# Motor_Driver.net
KiCad netlist of a schematic drawn in Altium Designer
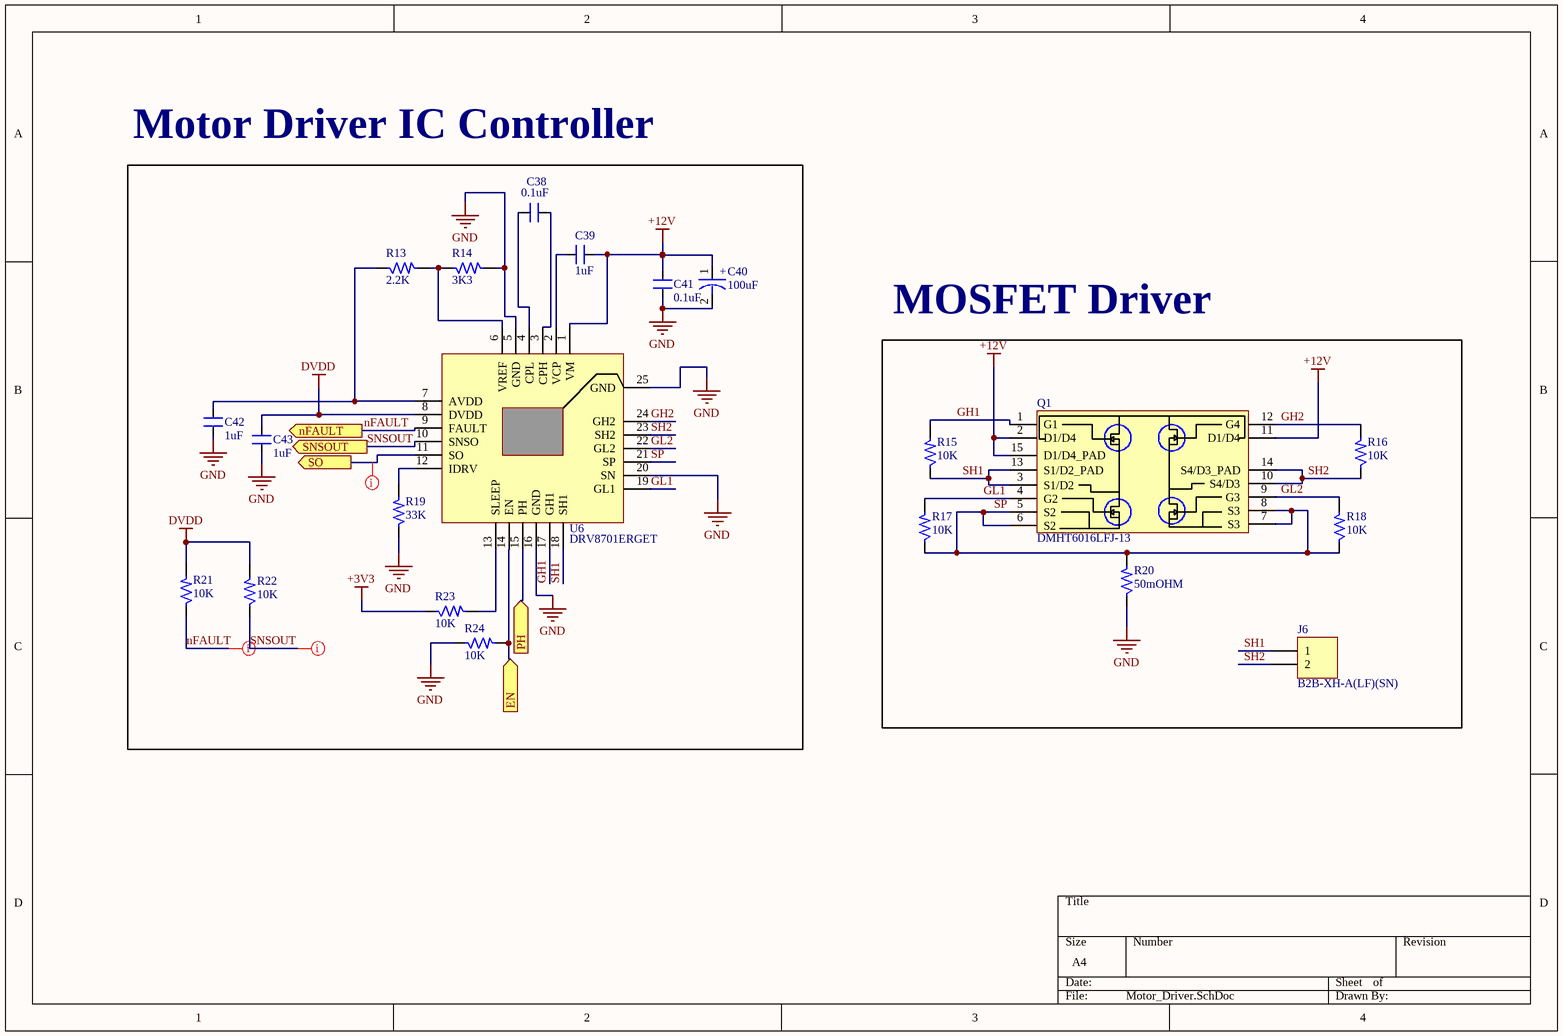
[diagram p0: Motor_Driver.SchDoc]

(export (version "E")
  (design (tool "Eeschema 10.0.6"))
  (components
    (comp (ref "C38")
      (value "0.1uF")
      (footprint "CAP_0805")
      (description "0.1µF ±10% 50V Ceramic Capacitor X7R 0805 (2012 Metric)")
      (fields
        (field (name "MANUFACTURER") "Samsung")
        (field (name "MANUFACTURER PART NUMBER") "CL21B104KBCNNNC")
      )
      (libsource (lib "STM32F407_Board") (part "CAP_0.1uF-50V-10%-0805"))
    )
    (comp (ref "C39")
      (value "1uF")
      (footprint "CAP_0805")
      (description "1µF ±5% 50V Ceramic Capacitor X7R 0805 (2012 Metric)")
      (fields
        (field (name "MANUFACTURER") "Samsung")
        (field (name "MANUFACTURER PART NUMBER") "CC0805JKX7R9BB105")
      )
      (libsource (lib "STM32F407_Board") (part "CAP_1uF-50V-5%-0805"))
    )
    (comp (ref "C40")
      (value "100uF")
      (footprint "ACAP_P305_D393_H393_RAD")
      (description "100µF 50V Aluminum Polymer Capacitor Radial, Can - SMD 28mOhm 4000 Hrs @ 125°C")
      (fields
        (field (name "MANUFACTURER") "Nichicon")
        (field (name "MANUFACTURER PART NUMBER") "GYA1H101MCQ1GS")
      )
      (libsource (lib "STM32F407_Board") (part "CAP-P_100uF-50V-20%-RAD"))
    )
    (comp (ref "C41")
      (value "0.1uF")
      (footprint "CAP_0805")
      (description "0.1µF ±10% 50V Ceramic Capacitor X7R 0805 (2012 Metric)")
      (fields
        (field (name "MANUFACTURER") "Samsung")
        (field (name "MANUFACTURER PART NUMBER") "CL21B104KBCNNNC")
      )
      (libsource (lib "STM32F407_Board") (part "CAP_0.1uF-50V-10%-0805"))
    )
    (comp (ref "C42")
      (value "1uF")
      (footprint "CAP_0805")
      (description "1µF ±5% 50V Ceramic Capacitor X7R 0805 (2012 Metric)")
      (fields
        (field (name "MANUFACTURER") "Samsung")
        (field (name "MANUFACTURER PART NUMBER") "CC0805JKX7R9BB105")
      )
      (libsource (lib "STM32F407_Board") (part "CAP_1uF-50V-5%-0805"))
    )
    (comp (ref "C43")
      (value "1uF")
      (footprint "CAP_0805")
      (description "1µF ±5% 50V Ceramic Capacitor X7R 0805 (2012 Metric)")
      (fields
        (field (name "MANUFACTURER") "Samsung")
        (field (name "MANUFACTURER PART NUMBER") "CC0805JKX7R9BB105")
      )
      (libsource (lib "STM32F407_Board") (part "CAP_1uF-50V-5%-0805"))
    )
    (comp (ref "J6")
      (value "B2B-XH-A(LF)(SN)")
      (footprint "CON2_100_B2B-XH-A_TH_ST")
      (description "2 Pins, 1 Row 2.54mm Pitch, Straight Connector, male")
      (fields (field (name "MANUFACTURER") "JST") (field (name "MATING PART NUMBER") "XHP-2"))
      (libsource (lib "STM32F407_Board") (part "CON-PLG_2X1-100-ST-TH"))
    )
    (comp (ref "Q1")
      (value "DMHT6016LFJ-13")
      (footprint "DFN5045-12_33_212_27X15_SMD_1")
      (description "Mosfet Array 4 N-Channel 14.8A (Ta) Surface Mount V-DFN5045-12")
      (fields (field (name "MANUFACTURER") "ON Semiconductor"))
      (libsource (lib "STM32F407_Board") (part "MOSFET-N_60V-14.8A-V-DFN5045-12"))
    )
    (comp (ref "R13")
      (value "2.2K")
      (footprint "RES_0603")
      (description "2.2 kOhms ±1% 0.1W, 1/10W Chip Resistor 0603 (1608 Metric) Automotive AEC-Q200 Thick Film")
      (fields (field (name "MANUFACTURER") "Walsin") (field (name "MANUFACTURER PART NUMBER") "WR06X2201FTL"))
      (libsource (lib "STM32F407_Board") (part "RES_2.2K-0.1W-1%-0603"))
    )
    (comp (ref "R14")
      (value "3K3")
      (footprint "RES_0603")
      (description "3.3 kOhms ±1% 0.1W, 1/10W Chip Resistor 0603 (1608 Metric) Automotive AEC-Q200 Thick Film")
      (fields (field (name "MANUFACTURER") "Wilson") (field (name "MANUFACTURER PART NUMBER") "WR06X3301FTL"))
      (libsource (lib "STM32F407_Board") (part "RES_3.3K-0.1W-1%-0603"))
    )
    (comp (ref "R15")
      (value "10K")
      (footprint "RES_0603")
      (description "10 kOhms ±1% 0.1W, 1/10W Chip Resistor 0603 (1608 Metric) Automotive AEC-Q200 Thick Film")
      (fields (field (name "MANUFACTURER") "Walsin") (field (name "MANUFACTURER PART NUMBER") "WR06X1002FTL"))
      (libsource (lib "STM32F407_Board") (part "RES_10K-0.1W-1%-0603"))
    )
    (comp (ref "R16")
      (value "10K")
      (footprint "RES_0603")
      (description "10 kOhms ±1% 0.1W, 1/10W Chip Resistor 0603 (1608 Metric) Automotive AEC-Q200 Thick Film")
      (fields (field (name "MANUFACTURER") "Walsin") (field (name "MANUFACTURER PART NUMBER") "WR06X1002FTL"))
      (libsource (lib "STM32F407_Board") (part "RES_10K-0.1W-1%-0603"))
    )
    (comp (ref "R17")
      (value "10K")
      (footprint "RES_0603")
      (description "10 kOhms ±1% 0.1W, 1/10W Chip Resistor 0603 (1608 Metric) Automotive AEC-Q200 Thick Film")
      (fields (field (name "MANUFACTURER") "Walsin") (field (name "MANUFACTURER PART NUMBER") "WR06X1002FTL"))
      (libsource (lib "STM32F407_Board") (part "RES_10K-0.1W-1%-0603"))
    )
    (comp (ref "R18")
      (value "10K")
      (footprint "RES_0603")
      (description "10 kOhms ±1% 0.1W, 1/10W Chip Resistor 0603 (1608 Metric) Automotive AEC-Q200 Thick Film")
      (fields (field (name "MANUFACTURER") "Walsin") (field (name "MANUFACTURER PART NUMBER") "WR06X1002FTL"))
      (libsource (lib "STM32F407_Board") (part "RES_10K-0.1W-1%-0603"))
    )
    (comp (ref "R19")
      (value "33K")
      (footprint "RES_0805")
      (fields
        (field (name "MANUFACTURER") "Vishay BCcomponents")
        (field (name "MANUFACTURER PART NUMBER") "CRG0805F33K")
      )
      (libsource (lib "STM32F407_Board") (part "RES_33K-0.125W-1%-0805"))
    )
    (comp (ref "R20")
      (value "50mOHM")
      (footprint "RES_2512")
      (fields
        (field (name "MANUFACTURER") "Yageo")
        (field (name "MANUFACTURER PART NUMBER") "PA2512FKF7W0R05E")
      )
      (libsource (lib "STM32F407_Board") (part "RES_50mOhm-2W-1%-2512"))
    )
    (comp (ref "R21")
      (value "10K")
      (footprint "RES_0603")
      (description "10 kOhms ±1% 0.1W, 1/10W Chip Resistor 0603 (1608 Metric) Automotive AEC-Q200 Thick Film")
      (fields (field (name "MANUFACTURER") "Walsin") (field (name "MANUFACTURER PART NUMBER") "WR06X1002FTL"))
      (libsource (lib "STM32F407_Board") (part "RES_10K-0.1W-1%-0603"))
    )
    (comp (ref "R22")
      (value "10K")
      (footprint "RES_0603")
      (description "10 kOhms ±1% 0.1W, 1/10W Chip Resistor 0603 (1608 Metric) Automotive AEC-Q200 Thick Film")
      (fields (field (name "MANUFACTURER") "Walsin") (field (name "MANUFACTURER PART NUMBER") "WR06X1002FTL"))
      (libsource (lib "STM32F407_Board") (part "RES_10K-0.1W-1%-0603"))
    )
    (comp (ref "R23")
      (value "10K")
      (footprint "RES_0603")
      (description "10 kOhms ±1% 0.1W, 1/10W Chip Resistor 0603 (1608 Metric) Automotive AEC-Q200 Thick Film")
      (fields (field (name "MANUFACTURER") "Walsin") (field (name "MANUFACTURER PART NUMBER") "WR06X1002FTL"))
      (libsource (lib "STM32F407_Board") (part "RES_10K-0.1W-1%-0603"))
    )
    (comp (ref "R24")
      (value "10K")
      (footprint "RES_0603")
      (description "10 kOhms ±1% 0.1W, 1/10W Chip Resistor 0603 (1608 Metric) Automotive AEC-Q200 Thick Film")
      (fields (field (name "MANUFACTURER") "Walsin") (field (name "MANUFACTURER PART NUMBER") "WR06X1002FTL"))
      (libsource (lib "STM32F407_Board") (part "RES_10K-0.1W-1%-0603"))
    )
    (comp (ref "U6")
      (value "DRV8701ERGET")
      (footprint "VFQFN24_19.6_196_12X32_SMD_1")
      (description "Motor Driver Power MOSFET Parallel 24-VQFN (4x4)")
      (fields (field (name "MANUFACTURER") "Texas Instruments"))
      (libsource (lib "STM32F407_Board") (part "IC_DRV8701ERGET"))
    )
  )
  (nets
    (net (code "1") (name "+3V3") (class "Default")
      (node (ref "R23") (pin "1") (pinfunction "1_1") (pintype "passive"))
    )
    (net (code "2") (name "+12V") (class "Default")
      (node (ref "C39") (pin "1") (pinfunction "1_1") (pintype "passive"))
      (node (ref "C40") (pin "1") (pinfunction "1_1") (pintype "passive"))
      (node (ref "C41") (pin "2") (pinfunction "2_2") (pintype "passive"))
      (node (ref "Q1") (pin "11") (pinfunction "D1/D4_11") (pintype "passive"))
      (node (ref "Q1") (pin "15") (pinfunction "D1/D4_PAD_15") (pintype "passive"))
      (node (ref "Q1") (pin "2") (pinfunction "D1/D4_2") (pintype "passive"))
      (node (ref "U6") (pin "1") (pinfunction "VM_1") (pintype "passive"))
    )
    (net (code "3") (name "/EN") (class "Default")
      (node (ref "R24") (pin "2") (pinfunction "2_2") (pintype "passive"))
      (node (ref "U6") (pin "14") (pinfunction "EN_14") (pintype "passive"))
    )
    (net (code "4") (name "/GH1") (class "Default")
      (node (ref "Q1") (pin "1") (pinfunction "G1_1") (pintype "passive"))
      (node (ref "R15") (pin "2") (pinfunction "2_2") (pintype "passive"))
      (node (ref "U6") (pin "17") (pinfunction "GH1_17") (pintype "passive"))
    )
    (net (code "5") (name "/GH2") (class "Default")
      (node (ref "Q1") (pin "12") (pinfunction "G4_12") (pintype "passive"))
      (node (ref "R16") (pin "2") (pinfunction "2_2") (pintype "passive"))
      (node (ref "U6") (pin "24") (pinfunction "GH2_24") (pintype "passive"))
    )
    (net (code "6") (name "/GL1") (class "Default")
      (node (ref "Q1") (pin "4") (pinfunction "G2_4") (pintype "passive"))
      (node (ref "R17") (pin "2") (pinfunction "2_2") (pintype "passive"))
      (node (ref "U6") (pin "19") (pinfunction "GL1_19") (pintype "passive"))
    )
    (net (code "7") (name "/GL2") (class "Default")
      (node (ref "Q1") (pin "9") (pinfunction "G3_9") (pintype "passive"))
      (node (ref "R18") (pin "2") (pinfunction "2_2") (pintype "passive"))
      (node (ref "U6") (pin "22") (pinfunction "GL2_22") (pintype "passive"))
    )
    (net (code "8") (name "/PH") (class "Default")
      (node (ref "U6") (pin "15") (pinfunction "PH_15") (pintype "passive"))
    )
    (net (code "9") (name "/SH1") (class "Default")
      (node (ref "J6") (pin "1") (pinfunction "1_1") (pintype "passive"))
      (node (ref "Q1") (pin "13") (pinfunction "S1/D2_PAD_13") (pintype "passive"))
      (node (ref "Q1") (pin "3") (pinfunction "S1/D2_3") (pintype "passive"))
      (node (ref "R15") (pin "1") (pinfunction "1_1") (pintype "passive"))
      (node (ref "U6") (pin "18") (pinfunction "SH1_18") (pintype "passive"))
    )
    (net (code "10") (name "/SH2") (class "Default")
      (node (ref "J6") (pin "2") (pinfunction "2_2") (pintype "passive"))
      (node (ref "Q1") (pin "10") (pinfunction "S4/D3_10") (pintype "passive"))
      (node (ref "Q1") (pin "14") (pinfunction "S4/D3_PAD_14") (pintype "passive"))
      (node (ref "R16") (pin "1") (pinfunction "1_1") (pintype "passive"))
      (node (ref "U6") (pin "23") (pinfunction "SH2_23") (pintype "passive"))
    )
    (net (code "11") (name "/SNSOUT") (class "Default")
      (node (ref "R22") (pin "1") (pinfunction "1_1") (pintype "passive"))
      (node (ref "U6") (pin "10") (pinfunction "SNSO_10") (pintype "passive"))
    )
    (net (code "12") (name "/SO") (class "Default")
      (node (ref "U6") (pin "11") (pinfunction "SO_11") (pintype "passive"))
    )
    (net (code "13") (name "/SP") (class "Default")
      (node (ref "Q1") (pin "5") (pinfunction "S2_5") (pintype "passive"))
      (node (ref "Q1") (pin "6") (pinfunction "S2_6") (pintype "passive"))
      (node (ref "Q1") (pin "7") (pinfunction "S3_7") (pintype "passive"))
      (node (ref "Q1") (pin "8") (pinfunction "S3_8") (pintype "passive"))
      (node (ref "R17") (pin "1") (pinfunction "1_1") (pintype "passive"))
      (node (ref "R18") (pin "1") (pinfunction "1_1") (pintype "passive"))
      (node (ref "R20") (pin "2") (pinfunction "2_2") (pintype "passive"))
      (node (ref "U6") (pin "21") (pinfunction "SP_21") (pintype "passive"))
    )
    (net (code "14") (name "/nFAULT") (class "Default")
      (node (ref "R21") (pin "1") (pinfunction "1_1") (pintype "passive"))
      (node (ref "U6") (pin "9") (pinfunction "FAULT_9") (pintype "passive"))
    )
    (net (code "15") (name "DVDD") (class "Default")
      (node (ref "C43") (pin "2") (pinfunction "2_2") (pintype "passive"))
      (node (ref "R21") (pin "2") (pinfunction "2_2") (pintype "passive"))
      (node (ref "R22") (pin "2") (pinfunction "2_2") (pintype "passive"))
      (node (ref "U6") (pin "8") (pinfunction "DVDD_8") (pintype "passive"))
    )
    (net (code "16") (name "GND") (class "Default")
      (node (ref "C40") (pin "2") (pinfunction "2_2") (pintype "passive"))
      (node (ref "C41") (pin "1") (pinfunction "1_1") (pintype "passive"))
      (node (ref "C42") (pin "1") (pinfunction "1_1") (pintype "passive"))
      (node (ref "C43") (pin "1") (pinfunction "1_1") (pintype "passive"))
      (node (ref "R14") (pin "2") (pinfunction "2_2") (pintype "passive"))
      (node (ref "R19") (pin "1") (pinfunction "1_1") (pintype "passive"))
      (node (ref "R20") (pin "1") (pinfunction "1_1") (pintype "passive"))
      (node (ref "R24") (pin "1") (pinfunction "1_1") (pintype "passive"))
      (node (ref "U6") (pin "16") (pinfunction "GND_16") (pintype "passive"))
      (node (ref "U6") (pin "20") (pinfunction "SN_20") (pintype "passive"))
      (node (ref "U6") (pin "25") (pinfunction "GND_25") (pintype "passive"))
      (node (ref "U6") (pin "5") (pinfunction "GND_5") (pintype "passive"))
    )
    (net (code "17") (name "Net-(U6-AVDD)") (class "Default")
      (node (ref "C42") (pin "2") (pinfunction "2_2") (pintype "passive"))
      (node (ref "R13") (pin "1") (pinfunction "1_1") (pintype "passive"))
      (node (ref "U6") (pin "7") (pinfunction "AVDD_7") (pintype "passive"))
    )
    (net (code "18") (name "Net-(U6-CPH)") (class "Default")
      (node (ref "C38") (pin "1") (pinfunction "1_1") (pintype "passive"))
      (node (ref "U6") (pin "3") (pinfunction "CPH_3") (pintype "passive"))
    )
    (net (code "19") (name "Net-(U6-CPL)") (class "Default")
      (node (ref "C38") (pin "2") (pinfunction "2_2") (pintype "passive"))
      (node (ref "U6") (pin "4") (pinfunction "CPL_4") (pintype "passive"))
    )
    (net (code "20") (name "Net-(U6-IDRV)") (class "Default")
      (node (ref "R19") (pin "2") (pinfunction "2_2") (pintype "passive"))
      (node (ref "U6") (pin "12") (pinfunction "IDRV_12") (pintype "passive"))
    )
    (net (code "21") (name "Net-(U6-SLEEP)") (class "Default")
      (node (ref "R23") (pin "2") (pinfunction "2_2") (pintype "passive"))
      (node (ref "U6") (pin "13") (pinfunction "SLEEP_13") (pintype "passive"))
    )
    (net (code "22") (name "Net-(U6-VCP)") (class "Default")
      (node (ref "C39") (pin "2") (pinfunction "2_2") (pintype "passive"))
      (node (ref "U6") (pin "2") (pinfunction "VCP_2") (pintype "passive"))
    )
    (net (code "23") (name "Net-(U6-VREF)") (class "Default")
      (node (ref "R13") (pin "2") (pinfunction "2_2") (pintype "passive"))
      (node (ref "R14") (pin "1") (pinfunction "1_1") (pintype "passive"))
      (node (ref "U6") (pin "6") (pinfunction "VREF_6") (pintype "passive"))
    )
  )
)
